# CLKB_uplink_phy_and_sfp_1221.net
KiCad netlist of a schematic drawn in Altium Designer
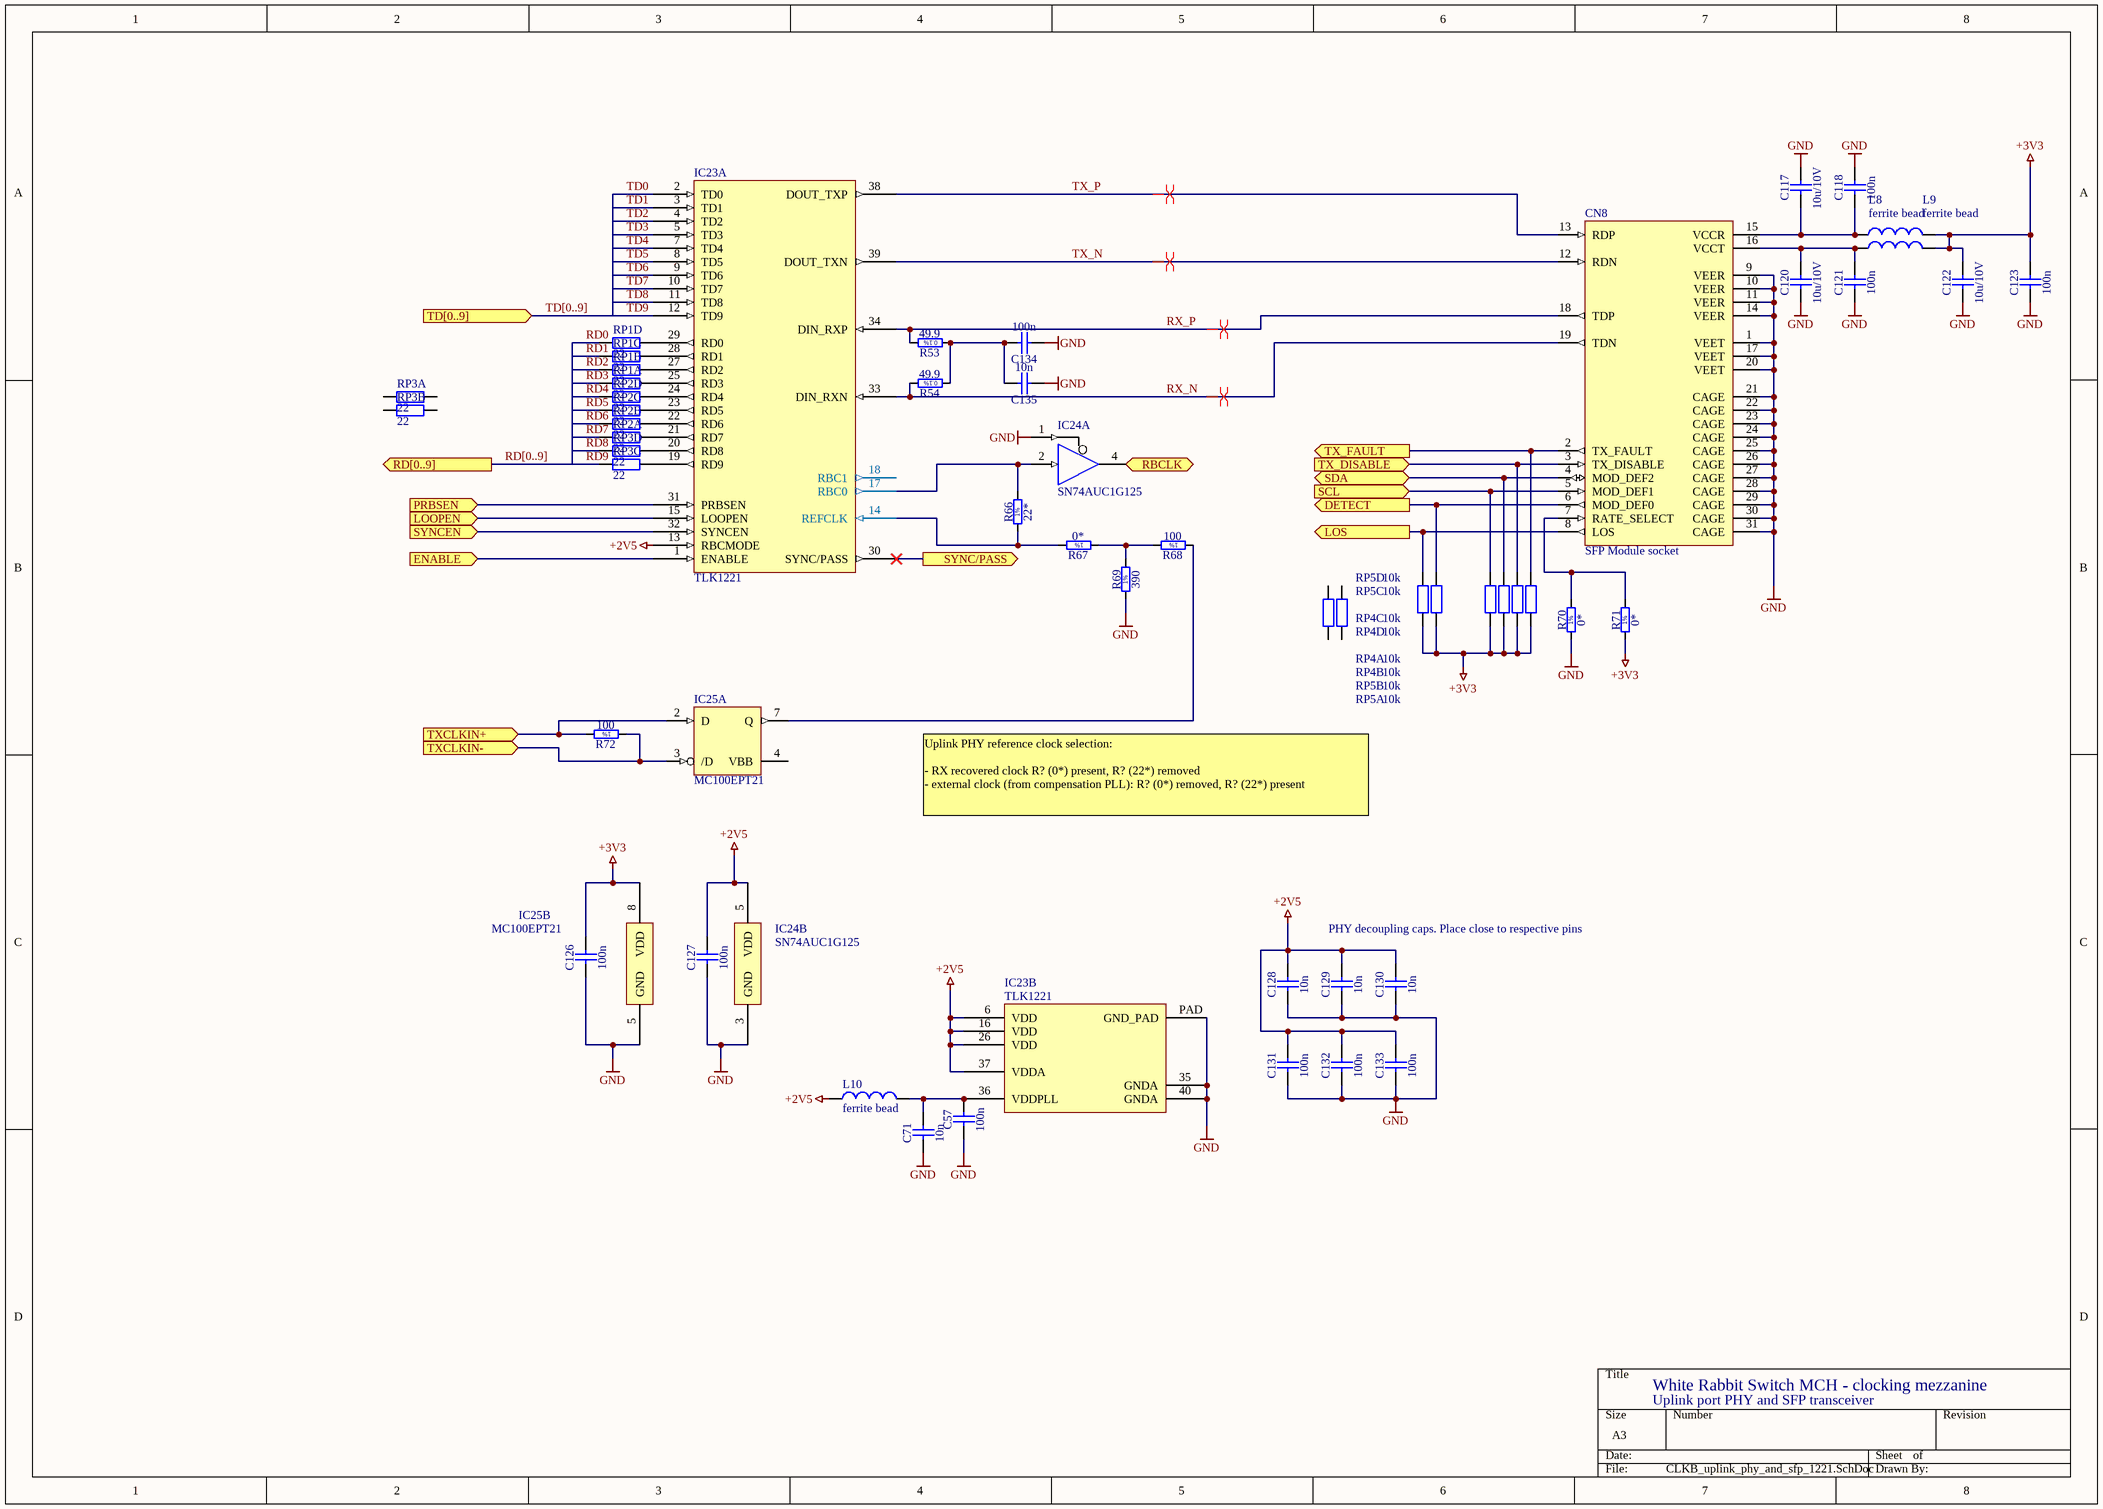
[diagram p0: CLKB_uplink_phy_and_sfp_1221.SchDoc]

(export (version "E")
  (design (tool "Eeschema 10.0.6"))
  (components
    (comp (ref "C57")
      (value "100n")
      (footprint "CAPC1608X87N")
      (description "Non-polarised capacitor")
      (fields
        (field (name "PART NUMBER") "CC0603_100NF_50V_10%_X7R")
        (field (name "VOLTAGE") "50V")
        (field (name "AUTHOR") "CERN DEM JLC")
      )
      (libsource (lib "Capacitors") (part "Capacitor - non polarized"))
    )
    (comp (ref "C71")
      (value "10n")
      (footprint "CAPC1608X87N")
      (description "Non-polarised capacitor")
      (fields
        (field (name "PART NUMBER") "CC0603_10NF_50V_10%_X7R")
        (field (name "VOLTAGE") "50V")
        (field (name "AUTHOR") "CERN DEM JLC")
      )
      (libsource (lib "Capacitors") (part "Capacitor - non polarized"))
    )
    (comp (ref "C117")
      (value "10u/10V")
      (footprint "CAPC3216X140N")
      (description "Non-polarised capacitor")
      (fields
        (field (name "PART NUMBER") "CC1206_10UF_10V_10%_X7R")
        (field (name "VOLTAGE") "10V")
        (field (name "AUTHOR") "CERN DEM JLC")
      )
      (libsource (lib "Capacitors") (part "Capacitor - non polarized"))
    )
    (comp (ref "C118")
      (value "100n")
      (footprint "CAPC1608X87N")
      (description "Non-polarised capacitor")
      (fields
        (field (name "PART NUMBER") "CC0603_100NF_50V_10%_X7R")
        (field (name "VOLTAGE") "50V")
        (field (name "AUTHOR") "CERN DEM JLC")
      )
      (libsource (lib "Capacitors") (part "Capacitor - non polarized"))
    )
    (comp (ref "C120")
      (value "10u/10V")
      (footprint "CAPC3216X140N")
      (description "Non-polarised capacitor")
      (fields
        (field (name "PART NUMBER") "CC1206_10UF_10V_10%_X7R")
        (field (name "VOLTAGE") "10V")
        (field (name "AUTHOR") "CERN DEM JLC")
      )
      (libsource (lib "Capacitors") (part "Capacitor - non polarized"))
    )
    (comp (ref "C121")
      (value "100n")
      (footprint "CAPC1608X87N")
      (description "Non-polarised capacitor")
      (fields
        (field (name "PART NUMBER") "CC0603_100NF_50V_10%_X7R")
        (field (name "VOLTAGE") "50V")
        (field (name "AUTHOR") "CERN DEM JLC")
      )
      (libsource (lib "Capacitors") (part "Capacitor - non polarized"))
    )
    (comp (ref "C122")
      (value "10u/10V")
      (footprint "CAPC3216X140N")
      (description "Non-polarised capacitor")
      (fields
        (field (name "PART NUMBER") "CC1206_10UF_10V_10%_X7R")
        (field (name "VOLTAGE") "10V")
        (field (name "AUTHOR") "CERN DEM JLC")
      )
      (libsource (lib "Capacitors") (part "Capacitor - non polarized"))
    )
    (comp (ref "C123")
      (value "100n")
      (footprint "CAPC1608X87N")
      (description "Non-polarised capacitor")
      (fields
        (field (name "PART NUMBER") "CC0603_100NF_50V_10%_X7R")
        (field (name "VOLTAGE") "50V")
        (field (name "AUTHOR") "CERN DEM JLC")
      )
      (libsource (lib "Capacitors") (part "Capacitor - non polarized"))
    )
    (comp (ref "C126")
      (value "100n")
      (footprint "CAPC1608X87N")
      (description "Non-polarised capacitor")
      (fields
        (field (name "PART NUMBER") "CC0603_100NF_50V_10%_X7R")
        (field (name "VOLTAGE") "50V")
        (field (name "AUTHOR") "CERN DEM JLC")
      )
      (libsource (lib "Capacitors") (part "Capacitor - non polarized"))
    )
    (comp (ref "C127")
      (value "100n")
      (footprint "CAPC1608X87N")
      (description "Non-polarised capacitor")
      (fields
        (field (name "PART NUMBER") "CC0603_100NF_50V_10%_X7R")
        (field (name "VOLTAGE") "50V")
        (field (name "AUTHOR") "CERN DEM JLC")
      )
      (libsource (lib "Capacitors") (part "Capacitor - non polarized"))
    )
    (comp (ref "C128")
      (value "10n")
      (footprint "CAPC1608X87N")
      (description "Non-polarised capacitor")
      (fields
        (field (name "PART NUMBER") "CC0603_10NF_50V_10%_X7R")
        (field (name "VOLTAGE") "50V")
        (field (name "AUTHOR") "CERN DEM JLC")
      )
      (libsource (lib "Capacitors") (part "Capacitor - non polarized"))
    )
    (comp (ref "C129")
      (value "10n")
      (footprint "CAPC1608X87N")
      (description "Non-polarised capacitor")
      (fields
        (field (name "PART NUMBER") "CC0603_10NF_50V_10%_X7R")
        (field (name "VOLTAGE") "50V")
        (field (name "AUTHOR") "CERN DEM JLC")
      )
      (libsource (lib "Capacitors") (part "Capacitor - non polarized"))
    )
    (comp (ref "C130")
      (value "10n")
      (footprint "CAPC1608X87N")
      (description "Non-polarised capacitor")
      (fields
        (field (name "PART NUMBER") "CC0603_10NF_50V_10%_X7R")
        (field (name "VOLTAGE") "50V")
        (field (name "AUTHOR") "CERN DEM JLC")
      )
      (libsource (lib "Capacitors") (part "Capacitor - non polarized"))
    )
    (comp (ref "C131")
      (value "100n")
      (footprint "CAPC1608X87N")
      (description "Non-polarised capacitor")
      (fields
        (field (name "PART NUMBER") "CC0603_100NF_50V_10%_X7R")
        (field (name "VOLTAGE") "50V")
        (field (name "AUTHOR") "CERN DEM JLC")
      )
      (libsource (lib "Capacitors") (part "Capacitor - non polarized"))
    )
    (comp (ref "C132")
      (value "100n")
      (footprint "CAPC1608X87N")
      (description "Non-polarised capacitor")
      (fields
        (field (name "PART NUMBER") "CC0603_100NF_50V_10%_X7R")
        (field (name "VOLTAGE") "50V")
        (field (name "AUTHOR") "CERN DEM JLC")
      )
      (libsource (lib "Capacitors") (part "Capacitor - non polarized"))
    )
    (comp (ref "C133")
      (value "100n")
      (footprint "CAPC1608X87N")
      (description "Non-polarised capacitor")
      (fields
        (field (name "PART NUMBER") "CC0603_100NF_50V_10%_X7R")
        (field (name "VOLTAGE") "50V")
        (field (name "AUTHOR") "CERN DEM JLC")
      )
      (libsource (lib "Capacitors") (part "Capacitor - non polarized"))
    )
    (comp (ref "C134")
      (value "100n")
      (footprint "CAPC1608X87N")
      (description "Non-polarised capacitor")
      (fields
        (field (name "PART NUMBER") "CC0603_100NF_50V_10%_X7R")
        (field (name "VOLTAGE") "50V")
        (field (name "AUTHOR") "CERN DEM JLC")
      )
      (libsource (lib "Capacitors") (part "Capacitor - non polarized"))
    )
    (comp (ref "C135")
      (value "10n")
      (footprint "CAPC1608X87N")
      (description "Non-polarised capacitor")
      (fields
        (field (name "PART NUMBER") "CC0603_10NF_50V_10%_X7R")
        (field (name "VOLTAGE") "50V")
        (field (name "AUTHOR") "CERN DEM JLC")
      )
      (libsource (lib "Capacitors") (part "Capacitor - non polarized"))
    )
    (comp (ref "CN8")
      (value "SFP Module socket")
      (footprint "SFP_SINGLE_PORT")
      (description "Socket for SFP module")
      (libsource (lib "wr_switch") (part "SFP_SOCKET_SINGLE"))
    )
    (comp (ref "IC23")
      (value "TLK1221")
      (footprint "QFN40_powerpad")
      (description "Texas Instruments Gigabit Ethernet PHY with deterministic clocking and LVPECL output interface")
      (libsource (lib "wr_switch") (part "TLK1221"))
    )
    (comp (ref "IC24")
      (value "SN74AUC1G125")
      (footprint "SOT23-5AL")
      (description "TI 2.5V single tri-state buffer")
      (libsource (lib "wr_switch") (part "SN74AUC1G125"))
    )
    (comp (ref "IC25")
      (value "MC100EPT21")
      (footprint "TSOP65P490-8AN")
      (description "ONSemi LVDS/LVPECL -> LVTTL/LVCMOS buffer")
      (libsource (lib "wr_switch") (part "MC100EPT21"))
    )
    (comp (ref "L8")
      (value "ferrite bead")
      (footprint "INDC2012-0805")
      (description "Ferrite bead")
      (fields (field (name "Comment") "Inductor") (field (name "PUBLISHER") "Altium Limited"))
      (libsource (lib "Miscellaneous Devices") (part "Inductor"))
    )
    (comp (ref "L9")
      (value "ferrite bead")
      (footprint "INDC2012-0805")
      (description "Ferrite bead")
      (fields (field (name "Comment") "Inductor") (field (name "PUBLISHER") "Altium Limited"))
      (libsource (lib "Miscellaneous Devices") (part "Inductor"))
    )
    (comp (ref "L10")
      (value "ferrite bead")
      (footprint "INDC2012-0805")
      (description "Ferrite bead")
      (fields (field (name "Comment") "Inductor") (field (name "PUBLISHER") "Altium Limited"))
      (libsource (lib "") (part "Inductor_1"))
    )
    (comp (ref "R53")
      (value "49.9")
      (footprint "RESC1608X55N")
      (description "Resistor - 0.1%")
      (fields
        (field (name "PART NUMBER") "R0603_49R9_0.1%_0.063W_10PPM")
        (field (name "POWER") "0.063W")
        (field (name "AUTHOR") "CERN DEM JLC")
      )
      (libsource (lib "Resistors") (part "Resistor - 0.1%"))
    )
    (comp (ref "R54")
      (value "49.9")
      (footprint "RESC1608X55N")
      (description "Resistor - 0.1%")
      (fields
        (field (name "PART NUMBER") "R0603_49R9_0.1%_0.063W_10PPM")
        (field (name "POWER") "0.063W")
        (field (name "AUTHOR") "CERN DEM JLC")
      )
      (libsource (lib "Resistors") (part "Resistor - 0.1%"))
    )
    (comp (ref "R66")
      (value "22*")
      (footprint "RESC1608X55N")
      (description "Resistor - 1%")
      (fields
        (field (name "PART NUMBER") "R0603_22R_1%_0.1W_100PPM")
        (field (name "POWER") "0.1W")
        (field (name "AUTHOR") "CERN DEM JLC")
      )
      (libsource (lib "Resistors") (part "Resistor - 1%"))
    )
    (comp (ref "R67")
      (value "0*")
      (footprint "RESC1608X55N")
      (description "Resistor - 1%")
      (fields
        (field (name "PART NUMBER") "R0603_0R_JUMPER")
        (field (name "MANUFACTURER") "GENERIC")
        (field (name "AUTHOR") "CERN DEM JLC")
      )
      (libsource (lib "Resistors") (part "Resistor - 1%"))
    )
    (comp (ref "R68")
      (value "100")
      (footprint "RESC1608X55N")
      (description "Resistor - 1%")
      (fields
        (field (name "PART NUMBER") "R0603_100R_1%_0.1W_100PPM")
        (field (name "POWER") "0.1W")
        (field (name "AUTHOR") "CERN DEM JLC")
      )
      (libsource (lib "Resistors") (part "Resistor - 1%"))
    )
    (comp (ref "R69")
      (value "390")
      (footprint "RESC1608X55N")
      (description "Resistor - 1%")
      (fields
        (field (name "PART NUMBER") "R0603_390R_1%_0.1W_100PPM")
        (field (name "POWER") "0.1W")
        (field (name "AUTHOR") "CERN DEM JLC")
      )
      (libsource (lib "Resistors") (part "Resistor - 1%"))
    )
    (comp (ref "R70")
      (value "0*")
      (footprint "RESC1608X55N")
      (description "Resistor - 1%")
      (fields
        (field (name "PART NUMBER") "R0603_0R_JUMPER")
        (field (name "MANUFACTURER") "GENERIC")
        (field (name "AUTHOR") "CERN DEM JLC")
      )
      (libsource (lib "Resistors") (part "Resistor - 1%"))
    )
    (comp (ref "R71")
      (value "0*")
      (footprint "RESC1608X55N")
      (description "Resistor - 1%")
      (fields
        (field (name "PART NUMBER") "R0603_0R_JUMPER")
        (field (name "MANUFACTURER") "GENERIC")
        (field (name "AUTHOR") "CERN DEM JLC")
      )
      (libsource (lib "Resistors") (part "Resistor - 1%"))
    )
    (comp (ref "R72")
      (value "100")
      (footprint "RESC1608X55N")
      (description "Resistor - 1%")
      (fields
        (field (name "PART NUMBER") "R0603_100R_1%_0.1W_100PPM")
        (field (name "POWER") "0.1W")
        (field (name "AUTHOR") "CERN DEM JLC")
      )
      (libsource (lib "Resistors") (part "Resistor - 1%"))
    )
    (comp (ref "RP1")
      (value "22")
      (footprint "YC124")
      (description "4-resistor pack")
      (fields (field (name "Comment") "RES_PACK"))
      (libsource (lib "wr_switch") (part "Res_Pack4_22R_YC124"))
    )
    (comp (ref "RP2")
      (value "22")
      (footprint "YC124")
      (description "4-resistor pack")
      (fields (field (name "Comment") "RES_PACK"))
      (libsource (lib "wr_switch") (part "Res_Pack4_22R_YC124"))
    )
    (comp (ref "RP3")
      (value "22")
      (footprint "YC124")
      (description "4-resistor pack")
      (fields (field (name "Comment") "RES_PACK"))
      (libsource (lib "wr_switch") (part "Res_Pack4_22R_YC124"))
    )
    (comp (ref "RP4")
      (value "10k")
      (footprint "YC124")
      (description "4-resistor pack")
      (fields (field (name "Comment") "RES_PACK"))
      (libsource (lib "wr_switch") (part "Res_Pack4_10k_YC124"))
    )
    (comp (ref "RP5")
      (value "10k")
      (footprint "YC124")
      (description "4-resistor pack")
      (fields (field (name "Comment") "RES_PACK"))
      (libsource (lib "wr_switch") (part "Res_Pack4_10k_YC124"))
    )
  )
  (nets
    (net (code "1") (name "+2V5") (class "Default")
      (node (ref "C127") (pin "2") (pinfunction "2_2") (pintype "passive"))
      (node (ref "C128") (pin "2") (pinfunction "2_2") (pintype "passive"))
      (node (ref "C129") (pin "2") (pinfunction "2_2") (pintype "passive"))
      (node (ref "C130") (pin "2") (pinfunction "2_2") (pintype "passive"))
      (node (ref "C131") (pin "2") (pinfunction "2_2") (pintype "passive"))
      (node (ref "C132") (pin "2") (pinfunction "2_2") (pintype "passive"))
      (node (ref "C133") (pin "2") (pinfunction "2_2") (pintype "passive"))
      (node (ref "IC23") (pin "13") (pinfunction "RBCMODE_13") (pintype "input"))
      (node (ref "IC23") (pin "16") (pinfunction "VDD_16") (pintype "power_in"))
      (node (ref "IC23") (pin "26") (pinfunction "VDD_26") (pintype "power_in"))
      (node (ref "IC23") (pin "37") (pinfunction "VDDA_37") (pintype "power_in"))
      (node (ref "IC23") (pin "6") (pinfunction "VDD_6") (pintype "power_in"))
      (node (ref "IC24") (pin "5") (pinfunction "VDD_5") (pintype "passive"))
      (node (ref "L10") (pin "2") (pinfunction "2_2") (pintype "passive"))
    )
    (net (code "2") (name "+3V3") (class "Default")
      (node (ref "C122") (pin "2") (pinfunction "2_2") (pintype "passive"))
      (node (ref "C123") (pin "2") (pinfunction "2_2") (pintype "passive"))
      (node (ref "C126") (pin "2") (pinfunction "2_2") (pintype "passive"))
      (node (ref "IC25") (pin "8") (pinfunction "VDD_8") (pintype "passive"))
      (node (ref "L8") (pin "2") (pinfunction "2_2") (pintype "passive"))
      (node (ref "L9") (pin "2") (pinfunction "2_2") (pintype "passive"))
      (node (ref "R71") (pin "1") (pinfunction "1_1") (pintype "passive"))
      (node (ref "RP4") (pin "1") (pinfunction "A_1") (pintype "passive"))
      (node (ref "RP4") (pin "2") (pinfunction "A_2") (pintype "passive"))
      (node (ref "RP4") (pin "3") (pinfunction "A_3") (pintype "passive"))
      (node (ref "RP4") (pin "4") (pinfunction "A_4") (pintype "passive"))
      (node (ref "RP5") (pin "1") (pinfunction "A_1") (pintype "passive"))
      (node (ref "RP5") (pin "2") (pinfunction "A_2") (pintype "passive"))
    )
    (net (code "3") (name "/DETECT") (class "Default")
      (node (ref "CN8") (pin "6") (pinfunction "MOD_DEF0_6") (pintype "output"))
      (node (ref "RP4") (pin "6") (pinfunction "B_6") (pintype "passive"))
    )
    (net (code "4") (name "/ENABLE") (class "Default")
      (node (ref "IC23") (pin "1") (pinfunction "ENABLE_1") (pintype "input"))
    )
    (net (code "5") (name "/LOOPEN") (class "Default")
      (node (ref "IC23") (pin "15") (pinfunction "LOOPEN_15") (pintype "input"))
    )
    (net (code "6") (name "/LOS") (class "Default")
      (node (ref "CN8") (pin "8") (pinfunction "LOS_8") (pintype "output"))
      (node (ref "RP4") (pin "5") (pinfunction "B_5") (pintype "passive"))
    )
    (net (code "7") (name "/PRBSEN") (class "Default")
      (node (ref "IC23") (pin "31") (pinfunction "PRBSEN_31") (pintype "input"))
    )
    (net (code "8") (name "/RBCLK") (class "Default")
      (node (ref "IC24") (pin "4") (pinfunction "Y_4") (pintype "tri_state"))
    )
    (net (code "9") (name "/RD0") (class "Default")
      (node (ref "RP1") (pin "4") (pinfunction "A_4") (pintype "passive"))
    )
    (net (code "10") (name "/RD1") (class "Default")
      (node (ref "RP1") (pin "3") (pinfunction "A_3") (pintype "passive"))
    )
    (net (code "11") (name "/RD2") (class "Default")
      (node (ref "RP1") (pin "2") (pinfunction "A_2") (pintype "passive"))
    )
    (net (code "12") (name "/RD3") (class "Default")
      (node (ref "RP1") (pin "1") (pinfunction "A_1") (pintype "passive"))
    )
    (net (code "13") (name "/RD4") (class "Default")
      (node (ref "RP2") (pin "4") (pinfunction "A_4") (pintype "passive"))
    )
    (net (code "14") (name "/RD5") (class "Default")
      (node (ref "RP2") (pin "3") (pinfunction "A_3") (pintype "passive"))
    )
    (net (code "15") (name "/RD6") (class "Default")
      (node (ref "RP2") (pin "2") (pinfunction "A_2") (pintype "passive"))
    )
    (net (code "16") (name "/RD7") (class "Default")
      (node (ref "RP2") (pin "1") (pinfunction "A_1") (pintype "passive"))
    )
    (net (code "17") (name "/RD8") (class "Default")
      (node (ref "RP3") (pin "4") (pinfunction "A_4") (pintype "passive"))
    )
    (net (code "18") (name "/RD9") (class "Default")
      (node (ref "RP3") (pin "3") (pinfunction "A_3") (pintype "passive"))
    )
    (net (code "20") (name "/RX_N") (class "Default")
      (node (ref "CN8") (pin "19") (pinfunction "TDN_19") (pintype "output"))
      (node (ref "IC23") (pin "33") (pinfunction "DIN_RXN_33") (pintype "input"))
      (node (ref "R54") (pin "2") (pinfunction "2_2") (pintype "passive"))
    )
    (net (code "21") (name "/RX_P") (class "Default")
      (node (ref "CN8") (pin "18") (pinfunction "TDP_18") (pintype "output"))
      (node (ref "IC23") (pin "34") (pinfunction "DIN_RXP_34") (pintype "input"))
      (node (ref "R53") (pin "2") (pinfunction "2_2") (pintype "passive"))
    )
    (net (code "22") (name "/SCL") (class "Default")
      (node (ref "CN8") (pin "5") (pinfunction "MOD_DEF1_5") (pintype "input"))
      (node (ref "RP4") (pin "7") (pinfunction "B_7") (pintype "passive"))
    )
    (net (code "23") (name "/SDA") (class "Default")
      (node (ref "CN8") (pin "4") (pinfunction "MOD_DEF2_4") (pintype "bidirectional"))
      (node (ref "RP4") (pin "8") (pinfunction "B_8") (pintype "passive"))
    )
    (net (code "24") (name "/SYNCEN") (class "Default")
      (node (ref "IC23") (pin "32") (pinfunction "SYNCEN_32") (pintype "input"))
    )
    (net (code "25") (name "/SYNC{slash}PASS") (class "Default")
      (node (ref "IC23") (pin "30") (pinfunction "SYNC/PASS_30") (pintype "output+no_connect"))
    )
    (net (code "26") (name "/TD0") (class "Default")
      (node (ref "IC23") (pin "2") (pinfunction "TD0_2") (pintype "input"))
    )
    (net (code "27") (name "/TD1") (class "Default")
      (node (ref "IC23") (pin "3") (pinfunction "TD1_3") (pintype "input"))
    )
    (net (code "28") (name "/TD2") (class "Default")
      (node (ref "IC23") (pin "4") (pinfunction "TD2_4") (pintype "input"))
    )
    (net (code "29") (name "/TD3") (class "Default")
      (node (ref "IC23") (pin "5") (pinfunction "TD3_5") (pintype "input"))
    )
    (net (code "30") (name "/TD4") (class "Default")
      (node (ref "IC23") (pin "7") (pinfunction "TD4_7") (pintype "input"))
    )
    (net (code "31") (name "/TD5") (class "Default")
      (node (ref "IC23") (pin "8") (pinfunction "TD5_8") (pintype "input"))
    )
    (net (code "32") (name "/TD6") (class "Default")
      (node (ref "IC23") (pin "9") (pinfunction "TD6_9") (pintype "input"))
    )
    (net (code "33") (name "/TD7") (class "Default")
      (node (ref "IC23") (pin "10") (pinfunction "TD7_10") (pintype "input"))
    )
    (net (code "34") (name "/TD8") (class "Default")
      (node (ref "IC23") (pin "11") (pinfunction "TD8_11") (pintype "input"))
    )
    (net (code "35") (name "/TD9") (class "Default")
      (node (ref "IC23") (pin "12") (pinfunction "TD9_12") (pintype "input"))
    )
    (net (code "37") (name "/TXCLKIN+") (class "Default")
      (node (ref "IC25") (pin "2") (pinfunction "D_2") (pintype "input"))
      (node (ref "R72") (pin "2") (pinfunction "2_2") (pintype "passive"))
    )
    (net (code "38") (name "/TXCLKIN-") (class "Default")
      (node (ref "IC25") (pin "3") (pinfunction "/D_3") (pintype "input"))
      (node (ref "R72") (pin "1") (pinfunction "1_1") (pintype "passive"))
    )
    (net (code "39") (name "/TX_DISABLE") (class "Default")
      (node (ref "CN8") (pin "3") (pinfunction "TX_DISABLE_3") (pintype "input"))
      (node (ref "RP5") (pin "7") (pinfunction "B_7") (pintype "passive"))
    )
    (net (code "40") (name "/TX_FAULT") (class "Default")
      (node (ref "CN8") (pin "2") (pinfunction "TX_FAULT_2") (pintype "output"))
      (node (ref "RP5") (pin "8") (pinfunction "B_8") (pintype "passive"))
    )
    (net (code "41") (name "/TX_N") (class "Default")
      (node (ref "CN8") (pin "12") (pinfunction "RDN_12") (pintype "input"))
      (node (ref "IC23") (pin "39") (pinfunction "DOUT_TXN_39") (pintype "output"))
    )
    (net (code "42") (name "/TX_P") (class "Default")
      (node (ref "CN8") (pin "13") (pinfunction "RDP_13") (pintype "input"))
      (node (ref "IC23") (pin "38") (pinfunction "DOUT_TXP_38") (pintype "output"))
    )
    (net (code "43") (name "GND") (class "Default")
      (node (ref "C117") (pin "2") (pinfunction "2_2") (pintype "passive"))
      (node (ref "C118") (pin "2") (pinfunction "2_2") (pintype "passive"))
      (node (ref "C120") (pin "1") (pinfunction "1_1") (pintype "passive"))
      (node (ref "C121") (pin "1") (pinfunction "1_1") (pintype "passive"))
      (node (ref "C122") (pin "1") (pinfunction "1_1") (pintype "passive"))
      (node (ref "C123") (pin "1") (pinfunction "1_1") (pintype "passive"))
      (node (ref "C126") (pin "1") (pinfunction "1_1") (pintype "passive"))
      (node (ref "C127") (pin "1") (pinfunction "1_1") (pintype "passive"))
      (node (ref "C128") (pin "1") (pinfunction "1_1") (pintype "passive"))
      (node (ref "C129") (pin "1") (pinfunction "1_1") (pintype "passive"))
      (node (ref "C130") (pin "1") (pinfunction "1_1") (pintype "passive"))
      (node (ref "C131") (pin "1") (pinfunction "1_1") (pintype "passive"))
      (node (ref "C132") (pin "1") (pinfunction "1_1") (pintype "passive"))
      (node (ref "C133") (pin "1") (pinfunction "1_1") (pintype "passive"))
      (node (ref "C134") (pin "1") (pinfunction "1_1") (pintype "passive"))
      (node (ref "C135") (pin "1") (pinfunction "1_1") (pintype "passive"))
      (node (ref "C57") (pin "1") (pinfunction "1_1") (pintype "passive"))
      (node (ref "C71") (pin "1") (pinfunction "1_1") (pintype "passive"))
      (node (ref "CN8") (pin "1") (pinfunction "VEET_1") (pintype "power_in"))
      (node (ref "CN8") (pin "10") (pinfunction "VEER_10") (pintype "power_in"))
      (node (ref "CN8") (pin "11") (pinfunction "VEER_11") (pintype "power_in"))
      (node (ref "CN8") (pin "14") (pinfunction "VEER_14") (pintype "power_in"))
      (node (ref "CN8") (pin "17") (pinfunction "VEET_17") (pintype "power_in"))
      (node (ref "CN8") (pin "20") (pinfunction "VEET_20") (pintype "power_in"))
      (node (ref "CN8") (pin "21") (pinfunction "CAGE_21") (pintype "power_in"))
      (node (ref "CN8") (pin "22") (pinfunction "CAGE_22") (pintype "power_in"))
      (node (ref "CN8") (pin "23") (pinfunction "CAGE_23") (pintype "power_in"))
      (node (ref "CN8") (pin "24") (pinfunction "CAGE_24") (pintype "power_in"))
      (node (ref "CN8") (pin "25") (pinfunction "CAGE_25") (pintype "power_in"))
      (node (ref "CN8") (pin "26") (pinfunction "CAGE_26") (pintype "power_in"))
      (node (ref "CN8") (pin "27") (pinfunction "CAGE_27") (pintype "power_in"))
      (node (ref "CN8") (pin "28") (pinfunction "CAGE_28") (pintype "power_in"))
      (node (ref "CN8") (pin "29") (pinfunction "CAGE_29") (pintype "power_in"))
      (node (ref "CN8") (pin "30") (pinfunction "CAGE_30") (pintype "power_in"))
      (node (ref "CN8") (pin "31") (pinfunction "CAGE_31") (pintype "power_in"))
      (node (ref "CN8") (pin "9") (pinfunction "VEER_9") (pintype "power_in"))
      (node (ref "IC23") (pin "35") (pinfunction "GNDA_35") (pintype "power_in"))
      (node (ref "IC23") (pin "40") (pinfunction "GNDA_40") (pintype "power_in"))
      (node (ref "IC23") (pin "PAD") (pinfunction "GND_PAD_PAD") (pintype "power_in"))
      (node (ref "IC24") (pin "1") (pinfunction "~{OE}_1") (pintype "input"))
      (node (ref "IC24") (pin "3") (pinfunction "GND_3") (pintype "passive"))
      (node (ref "IC25") (pin "5") (pinfunction "GND_5") (pintype "passive"))
      (node (ref "R69") (pin "1") (pinfunction "1_1") (pintype "passive"))
      (node (ref "R70") (pin "1") (pinfunction "1_1") (pintype "passive"))
    )
    (net (code "44") (name "Net-(C134-Pad2)") (class "Default")
      (node (ref "C134") (pin "2") (pinfunction "2_2") (pintype "passive"))
      (node (ref "C135") (pin "2") (pinfunction "2_2") (pintype "passive"))
      (node (ref "R53") (pin "1") (pinfunction "1_1") (pintype "passive"))
      (node (ref "R54") (pin "1") (pinfunction "1_1") (pintype "passive"))
    )
    (net (code "45") (name "Net-(CN8-RATE_SELECT)") (class "Default")
      (node (ref "CN8") (pin "7") (pinfunction "RATE_SELECT_7") (pintype "input"))
      (node (ref "R70") (pin "2") (pinfunction "2_2") (pintype "passive"))
      (node (ref "R71") (pin "2") (pinfunction "2_2") (pintype "passive"))
    )
    (net (code "46") (name "Net-(CN8-VCCR)") (class "Default")
      (node (ref "C117") (pin "1") (pinfunction "1_1") (pintype "passive"))
      (node (ref "C118") (pin "1") (pinfunction "1_1") (pintype "passive"))
      (node (ref "CN8") (pin "15") (pinfunction "VCCR_15") (pintype "power_in"))
      (node (ref "L9") (pin "1") (pinfunction "1_1") (pintype "passive"))
    )
    (net (code "47") (name "Net-(CN8-VCCT)") (class "Default")
      (node (ref "C120") (pin "2") (pinfunction "2_2") (pintype "passive"))
      (node (ref "C121") (pin "2") (pinfunction "2_2") (pintype "passive"))
      (node (ref "CN8") (pin "16") (pinfunction "VCCT_16") (pintype "power_in"))
      (node (ref "L8") (pin "1") (pinfunction "1_1") (pintype "passive"))
    )
    (net (code "48") (name "Net-(IC23A-RBC0)") (class "Default")
      (node (ref "IC23") (pin "17") (pinfunction "RBC0_17") (pintype "output"))
      (node (ref "IC24") (pin "2") (pinfunction "A_2") (pintype "input"))
      (node (ref "R66") (pin "2") (pinfunction "2_2") (pintype "passive"))
    )
    (net (code "49") (name "Net-(IC23A-RD0)") (class "Default")
      (node (ref "IC23") (pin "29") (pinfunction "RD0_29") (pintype "output"))
      (node (ref "RP1") (pin "5") (pinfunction "B_5") (pintype "passive"))
    )
    (net (code "50") (name "Net-(IC23A-RD1)") (class "Default")
      (node (ref "IC23") (pin "28") (pinfunction "RD1_28") (pintype "output"))
      (node (ref "RP1") (pin "6") (pinfunction "B_6") (pintype "passive"))
    )
    (net (code "51") (name "Net-(IC23A-RD2)") (class "Default")
      (node (ref "IC23") (pin "27") (pinfunction "RD2_27") (pintype "output"))
      (node (ref "RP1") (pin "7") (pinfunction "B_7") (pintype "passive"))
    )
    (net (code "52") (name "Net-(IC23A-RD3)") (class "Default")
      (node (ref "IC23") (pin "25") (pinfunction "RD3_25") (pintype "output"))
      (node (ref "RP1") (pin "8") (pinfunction "B_8") (pintype "passive"))
    )
    (net (code "53") (name "Net-(IC23A-RD4)") (class "Default")
      (node (ref "IC23") (pin "24") (pinfunction "RD4_24") (pintype "output"))
      (node (ref "RP2") (pin "5") (pinfunction "B_5") (pintype "passive"))
    )
    (net (code "54") (name "Net-(IC23A-RD5)") (class "Default")
      (node (ref "IC23") (pin "23") (pinfunction "RD5_23") (pintype "output"))
      (node (ref "RP2") (pin "6") (pinfunction "B_6") (pintype "passive"))
    )
    (net (code "55") (name "Net-(IC23A-RD6)") (class "Default")
      (node (ref "IC23") (pin "22") (pinfunction "RD6_22") (pintype "output"))
      (node (ref "RP2") (pin "7") (pinfunction "B_7") (pintype "passive"))
    )
    (net (code "56") (name "Net-(IC23A-RD7)") (class "Default")
      (node (ref "IC23") (pin "21") (pinfunction "RD7_21") (pintype "output"))
      (node (ref "RP2") (pin "8") (pinfunction "B_8") (pintype "passive"))
    )
    (net (code "57") (name "Net-(IC23A-RD8)") (class "Default")
      (node (ref "IC23") (pin "20") (pinfunction "RD8_20") (pintype "output"))
      (node (ref "RP3") (pin "5") (pinfunction "B_5") (pintype "passive"))
    )
    (net (code "58") (name "Net-(IC23A-RD9)") (class "Default")
      (node (ref "IC23") (pin "19") (pinfunction "RD9_19") (pintype "output"))
      (node (ref "RP3") (pin "6") (pinfunction "B_6") (pintype "passive"))
    )
    (net (code "59") (name "Net-(IC23A-REFCLK)") (class "Default")
      (node (ref "IC23") (pin "14") (pinfunction "REFCLK_14") (pintype "input"))
      (node (ref "R66") (pin "1") (pinfunction "1_1") (pintype "passive"))
      (node (ref "R67") (pin "2") (pinfunction "2_2") (pintype "passive"))
    )
    (net (code "60") (name "Net-(IC23B-VDDPLL)") (class "Default")
      (node (ref "C57") (pin "2") (pinfunction "2_2") (pintype "passive"))
      (node (ref "C71") (pin "2") (pinfunction "2_2") (pintype "passive"))
      (node (ref "IC23") (pin "36") (pinfunction "VDDPLL_36") (pintype "power_in"))
      (node (ref "L10") (pin "1") (pinfunction "1_1") (pintype "passive"))
    )
    (net (code "61") (name "Net-(IC25A-Q)") (class "Default")
      (node (ref "IC25") (pin "7") (pinfunction "Q_7") (pintype "output"))
      (node (ref "R68") (pin "1") (pinfunction "1_1") (pintype "passive"))
    )
    (net (code "62") (name "Net-(R67-Pad1)") (class "Default")
      (node (ref "R67") (pin "1") (pinfunction "1_1") (pintype "passive"))
      (node (ref "R68") (pin "2") (pinfunction "2_2") (pintype "passive"))
      (node (ref "R69") (pin "2") (pinfunction "2_2") (pintype "passive"))
    )
    (net (code "63") (name "unconnected-(IC23A-RBC1-Pad18)") (class "Default")
      (node (ref "IC23") (pin "18") (pinfunction "RBC1_18") (pintype "output"))
    )
    (net (code "64") (name "unconnected-(IC25A-VBB-Pad4)") (class "Default")
      (node (ref "IC25") (pin "4") (pinfunction "VBB_4") (pintype "passive"))
    )
    (net (code "65") (name "unconnected-(RP3A-A-Pad1)") (class "Default")
      (node (ref "RP3") (pin "1") (pinfunction "A_1") (pintype "passive"))
    )
    (net (code "66") (name "unconnected-(RP3A-B-Pad8)") (class "Default")
      (node (ref "RP3") (pin "8") (pinfunction "B_8") (pintype "passive"))
    )
    (net (code "67") (name "unconnected-(RP3B-A-Pad2)") (class "Default")
      (node (ref "RP3") (pin "2") (pinfunction "A_2") (pintype "passive"))
    )
    (net (code "68") (name "unconnected-(RP3B-B-Pad7)") (class "Default")
      (node (ref "RP3") (pin "7") (pinfunction "B_7") (pintype "passive"))
    )
    (net (code "69") (name "unconnected-(RP5C-A-Pad3)") (class "Default")
      (node (ref "RP5") (pin "3") (pinfunction "A_3") (pintype "passive"))
    )
    (net (code "70") (name "unconnected-(RP5C-B-Pad6)") (class "Default")
      (node (ref "RP5") (pin "6") (pinfunction "B_6") (pintype "passive"))
    )
    (net (code "71") (name "unconnected-(RP5D-A-Pad4)") (class "Default")
      (node (ref "RP5") (pin "4") (pinfunction "A_4") (pintype "passive"))
    )
    (net (code "72") (name "unconnected-(RP5D-B-Pad5)") (class "Default")
      (node (ref "RP5") (pin "5") (pinfunction "B_5") (pintype "passive"))
    )
  )
)
